# Quad_FC_V10_2.net
KiCad netlist of a schematic drawn in Altium Designer
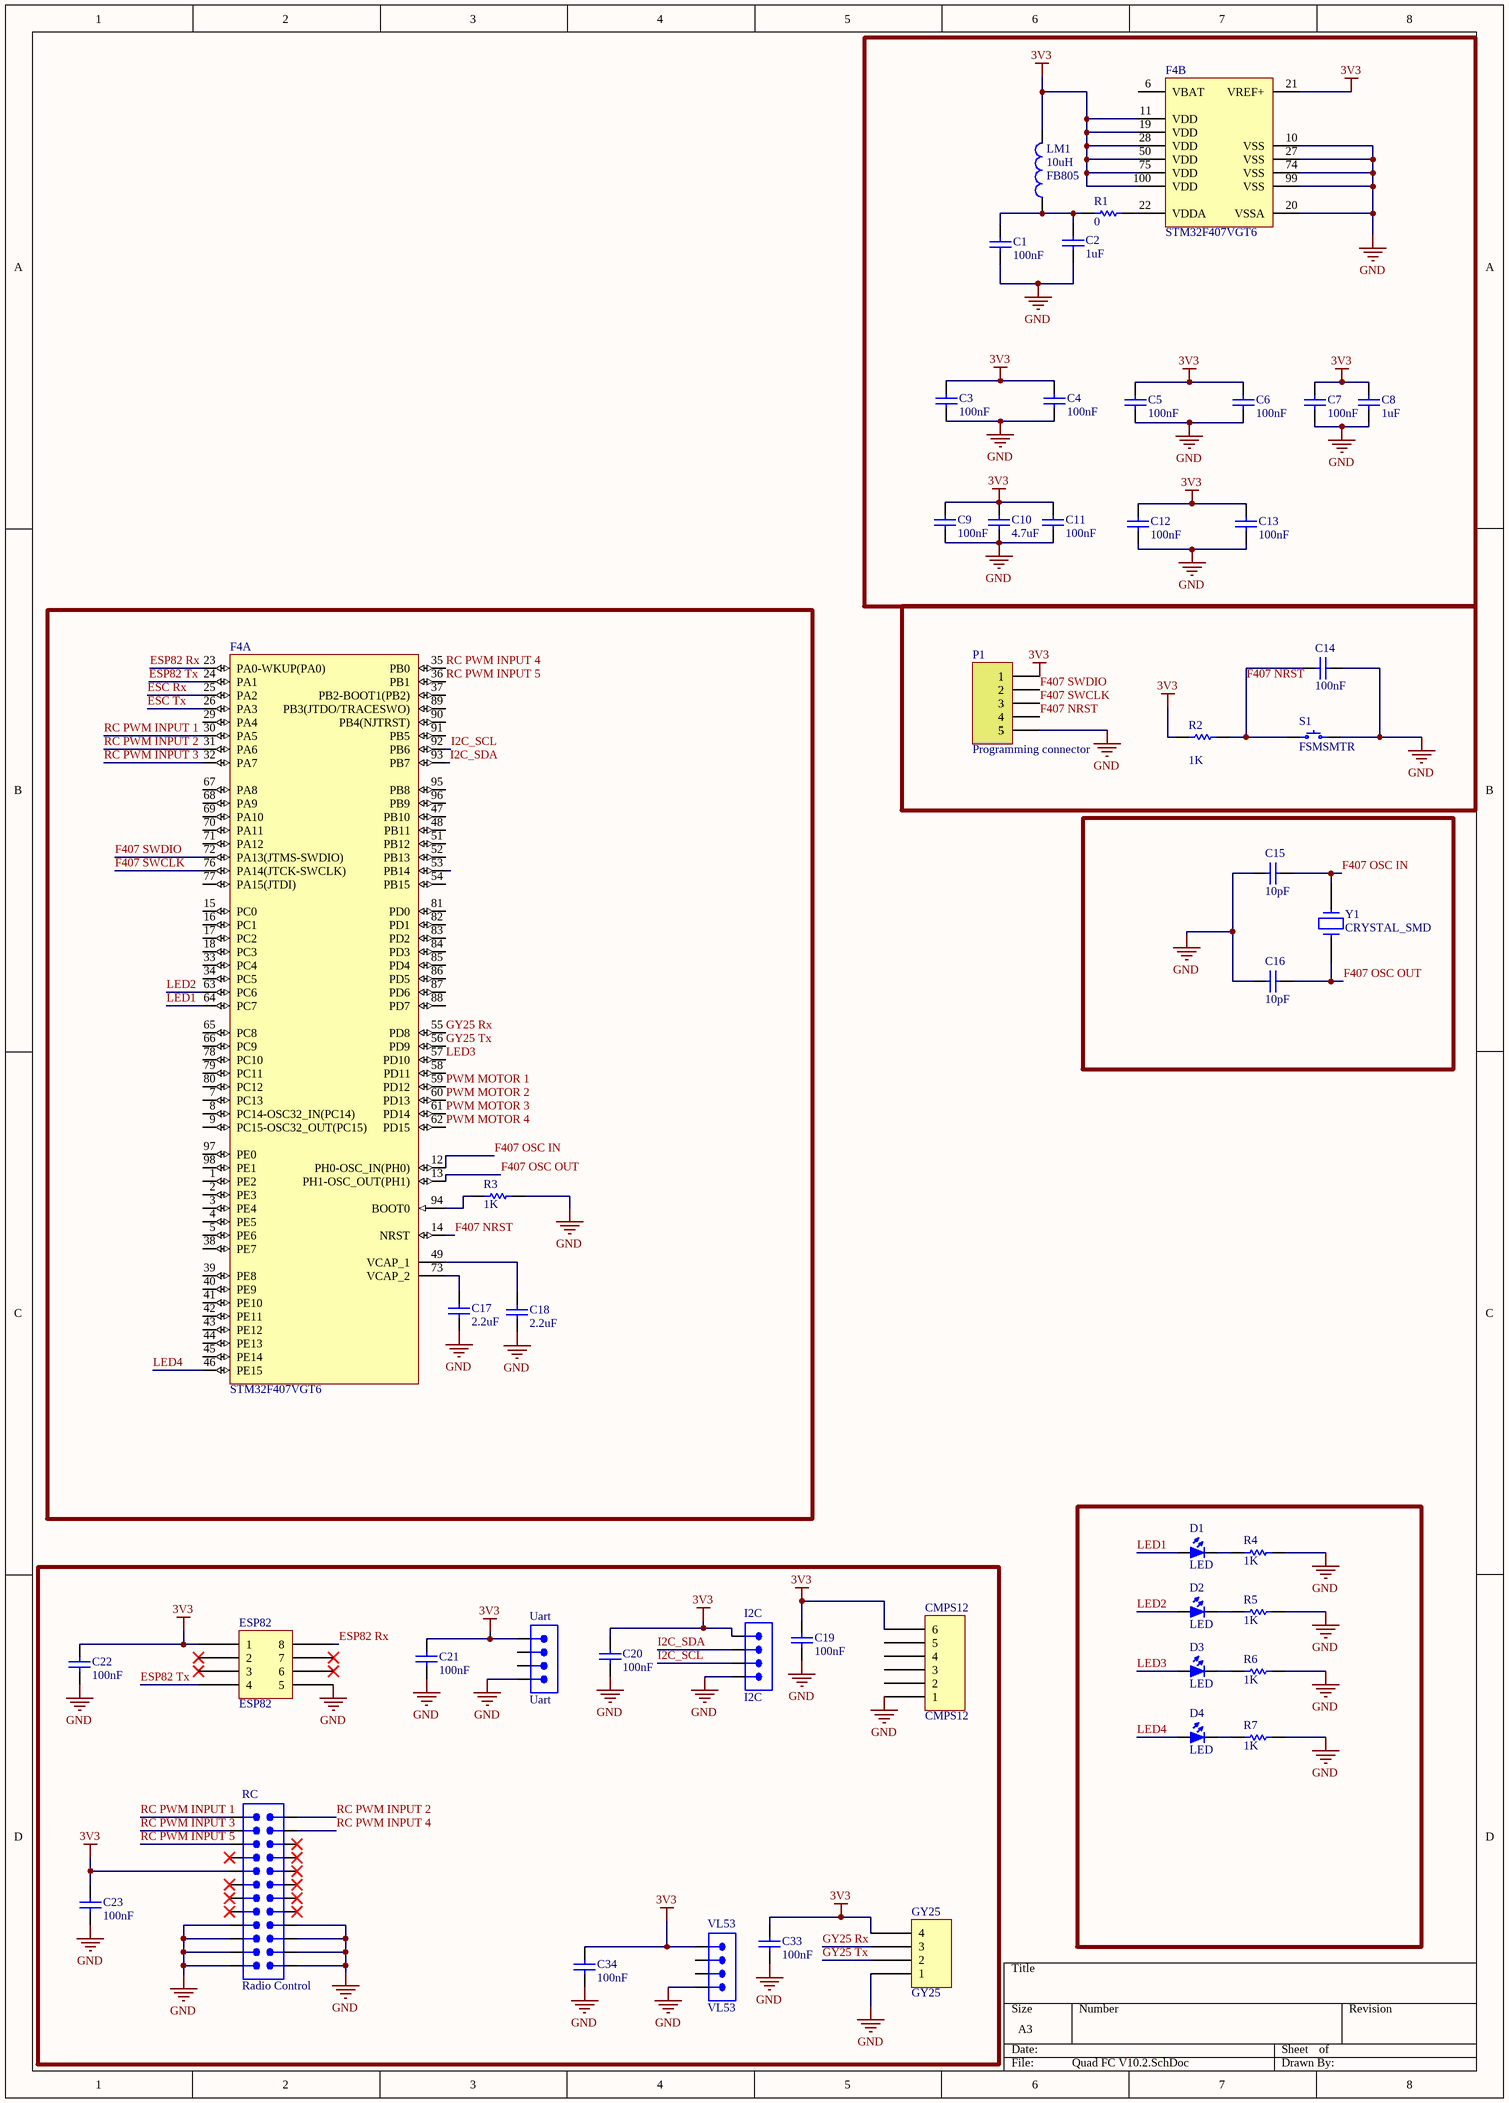
[diagram p0: Quad FC V10.2.SchDoc]

(export (version "E")
  (design (tool "Eeschema 10.0.6"))
  (components
    (comp (ref "C1")
      (value "100nF")
      (footprint "CAP0603")
      (description "F407VET6 Power CAP")
      (fields (field (name "DESIGNER") "Abbas Basereh"))
      (libsource (lib "2017AbbasBasereh9365731239 -ver1") (part "CAP SMD PACKAGE"))
    )
    (comp (ref "C2")
      (value "1uF")
      (footprint "CAP0603")
      (description "F407VET6 Power CAP")
      (fields (field (name "DESIGNER") "Abbas Basereh"))
      (libsource (lib "2017AbbasBasereh9365731239 -ver1") (part "CAP SMD PACKAGE"))
    )
    (comp (ref "C3")
      (value "100nF")
      (footprint "CAP0603")
      (description "F407VET6 Power CAP")
      (fields (field (name "DESIGNER") "Abbas Basereh"))
      (libsource (lib "2017AbbasBasereh9365731239 -ver1") (part "CAP SMD PACKAGE"))
    )
    (comp (ref "C4")
      (value "100nF")
      (footprint "CAP0603")
      (description "F407VET6 Power CAP")
      (fields (field (name "DESIGNER") "Abbas Basereh"))
      (libsource (lib "2017AbbasBasereh9365731239 -ver1") (part "CAP SMD PACKAGE"))
    )
    (comp (ref "C5")
      (value "100nF")
      (footprint "CAP0603")
      (description "F407VET6 Power CAP")
      (fields (field (name "DESIGNER") "Abbas Basereh"))
      (libsource (lib "2017AbbasBasereh9365731239 -ver1") (part "CAP SMD PACKAGE"))
    )
    (comp (ref "C6")
      (value "100nF")
      (footprint "CAP0603")
      (description "F407VET6 Power CAP")
      (fields (field (name "DESIGNER") "Abbas Basereh"))
      (libsource (lib "2017AbbasBasereh9365731239 -ver1") (part "CAP SMD PACKAGE"))
    )
    (comp (ref "C7")
      (value "100nF")
      (footprint "CAP0603")
      (description "F407VET6 Power CAP")
      (fields (field (name "DESIGNER") "Abbas Basereh"))
      (libsource (lib "2017AbbasBasereh9365731239 -ver1") (part "CAP SMD PACKAGE"))
    )
    (comp (ref "C8")
      (value "1uF")
      (footprint "CAP0603")
      (description "F407VET6 Power CAP")
      (fields (field (name "DESIGNER") "Abbas Basereh"))
      (libsource (lib "2017AbbasBasereh9365731239 -ver1") (part "CAP SMD PACKAGE"))
    )
    (comp (ref "C9")
      (value "100nF")
      (footprint "CAP0603")
      (description "F407VET6 Power CAP")
      (fields (field (name "DESIGNER") "Abbas Basereh"))
      (libsource (lib "2017AbbasBasereh9365731239 -ver1") (part "CAP SMD PACKAGE"))
    )
    (comp (ref "C10")
      (value "4.7uF")
      (footprint "CAP0603")
      (description "F407VET6 Power CAP")
      (fields (field (name "DESIGNER") "Abbas Basereh"))
      (libsource (lib "2017AbbasBasereh9365731239 -ver1") (part "CAP SMD PACKAGE"))
    )
    (comp (ref "C11")
      (value "100nF")
      (footprint "CAP0603")
      (description "F407VET6 Power CAP")
      (fields (field (name "DESIGNER") "Abbas Basereh"))
      (libsource (lib "2017AbbasBasereh9365731239 -ver1") (part "CAP SMD PACKAGE"))
    )
    (comp (ref "C12")
      (value "100nF")
      (footprint "CAP0603")
      (description "F407VET6 Power CAP")
      (fields (field (name "DESIGNER") "Abbas Basereh"))
      (libsource (lib "2017AbbasBasereh9365731239 -ver1") (part "CAP SMD PACKAGE"))
    )
    (comp (ref "C13")
      (value "100nF")
      (footprint "CAP0603")
      (description "F407VET6 Power CAP")
      (fields (field (name "DESIGNER") "Abbas Basereh"))
      (libsource (lib "2017AbbasBasereh9365731239 -ver1") (part "CAP SMD PACKAGE"))
    )
    (comp (ref "C14")
      (value "100nF")
      (footprint "CAP0603")
      (description "F407VET6 Power CAP")
      (fields (field (name "DESIGNER") "Abbas Basereh"))
      (libsource (lib "2017AbbasBasereh9365731239 -ver1") (part "CAP SMD PACKAGE"))
    )
    (comp (ref "C15")
      (value "10pF")
      (footprint "CAP0603")
      (description "F407VET6 Power CAP")
      (fields (field (name "DESIGNER") "Abbas Basereh"))
      (libsource (lib "2017AbbasBasereh9365731239 -ver1") (part "CAP SMD PACKAGE"))
    )
    (comp (ref "C16")
      (value "10pF")
      (footprint "CAP0603")
      (description "F407VET6 Power CAP")
      (fields (field (name "DESIGNER") "Abbas Basereh"))
      (libsource (lib "2017AbbasBasereh9365731239 -ver1") (part "CAP SMD PACKAGE"))
    )
    (comp (ref "C17")
      (value "2.2uF")
      (footprint "CAP0603")
      (description "F407VET6 Power CAP")
      (fields (field (name "DESIGNER") "Abbas Basereh"))
      (libsource (lib "2017AbbasBasereh9365731239 -ver1") (part "CAP SMD PACKAGE"))
    )
    (comp (ref "C18")
      (value "2.2uF")
      (footprint "CAP0603")
      (description "F407VET6 Power CAP")
      (fields (field (name "DESIGNER") "Abbas Basereh"))
      (libsource (lib "2017AbbasBasereh9365731239 -ver1") (part "CAP SMD PACKAGE"))
    )
    (comp (ref "C19")
      (value "100nF")
      (footprint "CAP0603")
      (description "F407VET6 Power CAP")
      (fields (field (name "DESIGNER") "Abbas Basereh"))
      (libsource (lib "2017AbbasBasereh9365731239 -ver1") (part "CAP SMD PACKAGE"))
    )
    (comp (ref "C20")
      (value "100nF")
      (footprint "CAP0603")
      (description "F407VET6 Power CAP")
      (fields (field (name "DESIGNER") "Abbas Basereh"))
      (libsource (lib "2017AbbasBasereh9365731239 -ver1") (part "CAP SMD PACKAGE"))
    )
    (comp (ref "C21")
      (value "100nF")
      (footprint "CAP0603")
      (description "F407VET6 Power CAP")
      (fields (field (name "DESIGNER") "Abbas Basereh"))
      (libsource (lib "2017AbbasBasereh9365731239 -ver1") (part "CAP SMD PACKAGE"))
    )
    (comp (ref "C22")
      (value "100nF")
      (footprint "CAP0603")
      (description "F407VET6 Power CAP")
      (fields (field (name "DESIGNER") "Abbas Basereh"))
      (libsource (lib "2017AbbasBasereh9365731239 -ver1") (part "CAP SMD PACKAGE"))
    )
    (comp (ref "C23")
      (value "100nF")
      (footprint "CAP0603")
      (description "F407VET6 Power CAP")
      (fields (field (name "DESIGNER") "Abbas Basereh"))
      (libsource (lib "2017AbbasBasereh9365731239 -ver1") (part "CAP SMD PACKAGE"))
    )
    (comp (ref "C33")
      (value "100nF")
      (footprint "CAP0603")
      (description "F407VET6 Power CAP")
      (fields (field (name "DESIGNER") "Abbas Basereh"))
      (libsource (lib "2017AbbasBasereh9365731239 -ver1") (part "CAP SMD PACKAGE"))
    )
    (comp (ref "C34")
      (value "100nF")
      (footprint "CAP0603")
      (description "F407VET6 Power CAP")
      (fields (field (name "DESIGNER") "Abbas Basereh"))
      (libsource (lib "2017AbbasBasereh9365731239 -ver1") (part "CAP SMD PACKAGE"))
    )
    (comp (ref "CMPS12")
      (value "CMPS12")
      (footprint "SAMTEC SSW-106-03-T-S")
      (description "CONN RCPT 6POS 0.1 TIN PCB")
      (fields (field (name "PART NUMBER") "SSW-106-03-T-S") (field (name "MANUFACTURER") "Samtec Inc."))
      (libsource (lib "Celestial Altium Library - altium_library (1)") (part "6 Pin"))
    )
    (comp (ref "D1")
      (value "LED")
      (footprint "0603 - LED")
      (description "Led")
      (fields (field (name "PUBLISHER") "Altium Limited"))
      (libsource (lib "Sajad_Altium_Library") (part "LED"))
    )
    (comp (ref "D2")
      (value "LED")
      (footprint "0603 - LED")
      (description "Led")
      (fields (field (name "PUBLISHER") "Altium Limited"))
      (libsource (lib "Sajad_Altium_Library") (part "LED"))
    )
    (comp (ref "D3")
      (value "LED")
      (footprint "0603 - LED")
      (description "Led")
      (fields (field (name "PUBLISHER") "Altium Limited"))
      (libsource (lib "Sajad_Altium_Library") (part "LED"))
    )
    (comp (ref "D4")
      (value "LED")
      (footprint "0603 - LED")
      (description "Led")
      (fields (field (name "PUBLISHER") "Altium Limited"))
      (libsource (lib "Sajad_Altium_Library") (part "LED"))
    )
    (comp (ref "ESP82")
      (value "ESP82")
      (footprint "HARWIN M20-7830445")
      (description "CONN RCPT 8POS 0.1 GOLD PCB")
      (fields (field (name "PART NUMBER") "M20-7830442") (field (name "MANUFACTURER") "Harwin Inc."))
      (libsource (lib "Celestial Altium Library - altium_library (1)") (part "2X4 PIN DU"))
    )
    (comp (ref "F4")
      (value "STM32F407VGT6")
      (footprint "STM-LQFP100_N")
      (fields (field (name "MANUFACTURER") "STMicroelectronics"))
      (libsource (lib "STMicroelectronics STM32 F4") (part "STM32F407VGT6"))
    )
    (comp (ref "GY25")
      (value "GY25")
      (footprint "SAMTEC SSW-104-03-T-S")
      (description "CONN RCPT 4POS 0.1 TIN PCB")
      (fields (field (name "PART NUMBER") "SSW-104-03-T-S") (field (name "MANUFACTURER") "Samtec Inc."))
      (libsource (lib "Celestial Altium Library - altium_library (1)") (part "4 Pin"))
    )
    (comp (ref "I2C")
      (value "I2C")
      (footprint "JST BM04B-SURS-TF")
      (description "Male Header 1X04")
      (libsource (lib "SJ Sockets & Connectors") (part "MHDR_1X04"))
    )
    (comp (ref "LM1")
      (value "10uH")
      (footprint "0805L")
      (description "Inductor")
      (fields (field (name "ALTIUM_VALUE") "FB805") (field (name "PUBLISHER") "Altium Limited"))
      (libsource (lib "2017AbbasBasereh9365731239 -ver1") (part "L SMA 0.25W"))
    )
    (comp (ref "P1")
      (value "Programming connector")
      (footprint "Connector1X5")
      (description "Connector, 5-Pin2.5mm")
      (fields (field (name "PUBLISHER") "Altium Limited"))
      (libsource (lib "Sajad_Altium_Library") (part "Connector1x5"))
    )
    (comp (ref "R1")
      (value "0")
      (footprint "RES0603")
      (description "TOTAL SMD RESISTOR PACK")
      (fields (field (name "DESIGNER") "Abbas Basereh"))
      (libsource (lib "2017AbbasBasereh9365731239 -ver1") (part "RES SMD PACKAGE"))
    )
    (comp (ref "R2")
      (value "1K")
      (footprint "RES0603")
      (description "TOTAL SMD RESISTOR PACK")
      (fields (field (name "DESIGNER") "Abbas Basereh"))
      (libsource (lib "2017AbbasBasereh9365731239 -ver1") (part "RES SMD PACKAGE"))
    )
    (comp (ref "R3")
      (value "1K")
      (footprint "RES0603")
      (description "TOTAL SMD RESISTOR PACK")
      (fields (field (name "DESIGNER") "Abbas Basereh"))
      (libsource (lib "2017AbbasBasereh9365731239 -ver1") (part "RES SMD PACKAGE"))
    )
    (comp (ref "R4")
      (value "1K")
      (footprint "RES0603")
      (description "TOTAL SMD RESISTOR PACK")
      (fields (field (name "DESIGNER") "Abbas Basereh"))
      (libsource (lib "2017AbbasBasereh9365731239 -ver1") (part "RES SMD PACKAGE"))
    )
    (comp (ref "R5")
      (value "1K")
      (footprint "RES0603")
      (description "TOTAL SMD RESISTOR PACK")
      (fields (field (name "DESIGNER") "Abbas Basereh"))
      (libsource (lib "2017AbbasBasereh9365731239 -ver1") (part "RES SMD PACKAGE"))
    )
    (comp (ref "R6")
      (value "1K")
      (footprint "RES0603")
      (description "TOTAL SMD RESISTOR PACK")
      (fields (field (name "DESIGNER") "Abbas Basereh"))
      (libsource (lib "2017AbbasBasereh9365731239 -ver1") (part "RES SMD PACKAGE"))
    )
    (comp (ref "R7")
      (value "1K")
      (footprint "RES0603")
      (description "TOTAL SMD RESISTOR PACK")
      (fields (field (name "DESIGNER") "Abbas Basereh"))
      (libsource (lib "2017AbbasBasereh9365731239 -ver1") (part "RES SMD PACKAGE"))
    )
    (comp (ref "RC")
      (value "Radio Control")
      (footprint "HEADER8X3:HEADER8X3")
      (description "Male Header 2X12")
      (libsource (lib "SJ Sockets & Connectors") (part "MHDR_2X12"))
    )
    (comp (ref "S1")
      (value "FSMSMTR")
      (footprint "TE FSMSMTR")
      (description "SWITCH TACTILE SPST-NO 0.05A 24V")
      (fields (field (name "MANUFACTURER") "TE Connectivity ALCOSWITCH Switches"))
      (libsource (lib "Celestial Altium Library - altium_library (1)") (part "SPST-NO 2 PIN"))
    )
    (comp (ref "Uart")
      (value "Uart")
      (footprint "JST BM04B-SURS-TF")
      (description "Male Header 1X04")
      (libsource (lib "SJ Sockets & Connectors") (part "MHDR_1X04"))
    )
    (comp (ref "VL53")
      (value "VL53")
      (footprint "JST BM04B-SURS-TF")
      (description "Male Header 1X04")
      (libsource (lib "SJ Sockets & Connectors") (part "MHDR_1X04"))
    )
    (comp (ref "Y1")
      (value "CRYSTAL_SMD")
      (footprint "My_Crystal - SMD")
      (description "Crystal")
      (libsource (lib "AMINLIB") (part "CRYSTAL_SMD"))
    )
  )
  (nets
    (net (code "1") (name "/ESC Rx") (class "Default")
      (node (ref "F4") (pin "25") (pinfunction "PA2_25") (pintype "bidirectional"))
    )
    (net (code "2") (name "/ESC Tx") (class "Default")
      (node (ref "F4") (pin "26") (pinfunction "PA3_26") (pintype "bidirectional"))
    )
    (net (code "3") (name "/ESP82 Rx") (class "Default")
      (node (ref "ESP82") (pin "8") (pinfunction "8_8") (pintype "passive"))
      (node (ref "F4") (pin "23") (pinfunction "PA0-WKUP(PA0)_23") (pintype "bidirectional"))
    )
    (net (code "4") (name "/ESP82 Tx") (class "Default")
      (node (ref "ESP82") (pin "4") (pinfunction "4_4") (pintype "passive"))
      (node (ref "F4") (pin "24") (pinfunction "PA1_24") (pintype "bidirectional"))
    )
    (net (code "5") (name "/F407 NRST") (class "Default")
      (node (ref "C14") (pin "1") (pinfunction "1_1") (pintype "passive"))
      (node (ref "F4") (pin "14") (pinfunction "NRST_14") (pintype "bidirectional"))
      (node (ref "P1") (pin "4") (pinfunction "4_4") (pintype "passive"))
      (node (ref "R2") (pin "2") (pinfunction "2_2") (pintype "passive"))
      (node (ref "S1") (pin "1") (pinfunction "1_1") (pintype "passive"))
    )
    (net (code "6") (name "/F407 OSC IN") (class "Default")
      (node (ref "C15") (pin "2") (pinfunction "2_2") (pintype "passive"))
      (node (ref "F4") (pin "12") (pinfunction "PH0-OSC_IN(PH0)_12") (pintype "bidirectional"))
      (node (ref "Y1") (pin "2") (pinfunction "2_2") (pintype "passive"))
    )
    (net (code "7") (name "/F407 OSC OUT") (class "Default")
      (node (ref "C16") (pin "1") (pinfunction "1_1") (pintype "passive"))
      (node (ref "F4") (pin "13") (pinfunction "PH1-OSC_OUT(PH1)_13") (pintype "bidirectional"))
      (node (ref "Y1") (pin "1") (pinfunction "1_1") (pintype "passive"))
    )
    (net (code "8") (name "/F407 SWCLK") (class "Default")
      (node (ref "F4") (pin "76") (pinfunction "PA14(JTCK-SWCLK)_76") (pintype "bidirectional"))
      (node (ref "P1") (pin "3") (pinfunction "3_3") (pintype "passive"))
    )
    (net (code "9") (name "/F407 SWDIO") (class "Default")
      (node (ref "F4") (pin "72") (pinfunction "PA13(JTMS-SWDIO)_72") (pintype "bidirectional"))
      (node (ref "P1") (pin "2") (pinfunction "2_2") (pintype "passive"))
    )
    (net (code "10") (name "/GY25 Rx") (class "Default")
      (node (ref "F4") (pin "55") (pinfunction "PD8_55") (pintype "bidirectional"))
      (node (ref "GY25") (pin "3") (pinfunction "3_3") (pintype "passive"))
    )
    (net (code "11") (name "/GY25 Tx") (class "Default")
      (node (ref "F4") (pin "56") (pinfunction "PD9_56") (pintype "bidirectional"))
      (node (ref "GY25") (pin "2") (pinfunction "2_2") (pintype "passive"))
    )
    (net (code "12") (name "/I2C_SCL") (class "Default")
      (node (ref "F4") (pin "92") (pinfunction "PB6_92") (pintype "bidirectional"))
      (node (ref "I2C") (pin "3") (pinfunction "3_3") (pintype "passive"))
    )
    (net (code "13") (name "/I2C_SDA") (class "Default")
      (node (ref "F4") (pin "93") (pinfunction "PB7_93") (pintype "bidirectional"))
      (node (ref "I2C") (pin "2") (pinfunction "2_2") (pintype "passive"))
    )
    (net (code "14") (name "/LED1") (class "Default")
      (node (ref "D1") (pin "1") (pinfunction "A_1") (pintype "passive"))
      (node (ref "F4") (pin "64") (pinfunction "PC7_64") (pintype "bidirectional"))
    )
    (net (code "15") (name "/LED2") (class "Default")
      (node (ref "D2") (pin "1") (pinfunction "A_1") (pintype "passive"))
      (node (ref "F4") (pin "63") (pinfunction "PC6_63") (pintype "bidirectional"))
    )
    (net (code "16") (name "/LED3") (class "Default")
      (node (ref "D3") (pin "1") (pinfunction "A_1") (pintype "passive"))
      (node (ref "F4") (pin "57") (pinfunction "PD10_57") (pintype "bidirectional"))
    )
    (net (code "17") (name "/LED4") (class "Default")
      (node (ref "D4") (pin "1") (pinfunction "A_1") (pintype "passive"))
      (node (ref "F4") (pin "46") (pinfunction "PE15_46") (pintype "bidirectional"))
    )
    (net (code "18") (name "/PWM MOTOR 1") (class "Default")
      (node (ref "F4") (pin "59") (pinfunction "PD12_59") (pintype "bidirectional"))
    )
    (net (code "19") (name "/PWM MOTOR 2") (class "Default")
      (node (ref "F4") (pin "60") (pinfunction "PD13_60") (pintype "bidirectional"))
    )
    (net (code "20") (name "/PWM MOTOR 3") (class "Default")
      (node (ref "F4") (pin "61") (pinfunction "PD14_61") (pintype "bidirectional"))
    )
    (net (code "21") (name "/PWM MOTOR 4") (class "Default")
      (node (ref "F4") (pin "62") (pinfunction "PD15_62") (pintype "bidirectional"))
    )
    (net (code "22") (name "/RC PWM INPUT 1") (class "Default")
      (node (ref "F4") (pin "30") (pinfunction "PA5_30") (pintype "bidirectional"))
      (node (ref "RC") (pin "1") (pinfunction "1_1") (pintype "passive"))
    )
    (net (code "23") (name "/RC PWM INPUT 2") (class "Default")
      (node (ref "F4") (pin "31") (pinfunction "PA6_31") (pintype "bidirectional"))
      (node (ref "RC") (pin "2") (pinfunction "2_2") (pintype "passive"))
    )
    (net (code "24") (name "/RC PWM INPUT 3") (class "Default")
      (node (ref "F4") (pin "32") (pinfunction "PA7_32") (pintype "bidirectional"))
      (node (ref "RC") (pin "3") (pinfunction "3_3") (pintype "passive"))
    )
    (net (code "25") (name "/RC PWM INPUT 4") (class "Default")
      (node (ref "F4") (pin "35") (pinfunction "PB0_35") (pintype "bidirectional"))
      (node (ref "RC") (pin "4") (pinfunction "4_4") (pintype "passive"))
    )
    (net (code "26") (name "/RC PWM INPUT 5") (class "Default")
      (node (ref "F4") (pin "36") (pinfunction "PB1_36") (pintype "bidirectional"))
      (node (ref "RC") (pin "5") (pinfunction "5_5") (pintype "passive"))
    )
    (net (code "27") (name "3V3") (class "Default")
      (node (ref "C10") (pin "2") (pinfunction "2_2") (pintype "passive"))
      (node (ref "C11") (pin "2") (pinfunction "2_2") (pintype "passive"))
      (node (ref "C12") (pin "2") (pinfunction "2_2") (pintype "passive"))
      (node (ref "C13") (pin "2") (pinfunction "2_2") (pintype "passive"))
      (node (ref "C19") (pin "1") (pinfunction "1_1") (pintype "passive"))
      (node (ref "C20") (pin "1") (pinfunction "1_1") (pintype "passive"))
      (node (ref "C21") (pin "1") (pinfunction "1_1") (pintype "passive"))
      (node (ref "C22") (pin "1") (pinfunction "1_1") (pintype "passive"))
      (node (ref "C23") (pin "1") (pinfunction "1_1") (pintype "passive"))
      (node (ref "C3") (pin "2") (pinfunction "2_2") (pintype "passive"))
      (node (ref "C33") (pin "1") (pinfunction "1_1") (pintype "passive"))
      (node (ref "C34") (pin "1") (pinfunction "1_1") (pintype "passive"))
      (node (ref "C4") (pin "2") (pinfunction "2_2") (pintype "passive"))
      (node (ref "C5") (pin "2") (pinfunction "2_2") (pintype "passive"))
      (node (ref "C6") (pin "2") (pinfunction "2_2") (pintype "passive"))
      (node (ref "C7") (pin "1") (pinfunction "1_1") (pintype "passive"))
      (node (ref "C8") (pin "1") (pinfunction "1_1") (pintype "passive"))
      (node (ref "C9") (pin "2") (pinfunction "2_2") (pintype "passive"))
      (node (ref "CMPS12") (pin "6") (pinfunction "6_6") (pintype "passive"))
      (node (ref "ESP82") (pin "1") (pinfunction "1_1") (pintype "passive"))
      (node (ref "F4") (pin "100") (pinfunction "VDD_100") (pintype "power_in"))
      (node (ref "F4") (pin "11") (pinfunction "VDD_11") (pintype "power_in"))
      (node (ref "F4") (pin "19") (pinfunction "VDD_19") (pintype "power_in"))
      (node (ref "F4") (pin "21") (pinfunction "VREF+_21") (pintype "power_in"))
      (node (ref "F4") (pin "28") (pinfunction "VDD_28") (pintype "power_in"))
      (node (ref "F4") (pin "50") (pinfunction "VDD_50") (pintype "power_in"))
      (node (ref "F4") (pin "75") (pinfunction "VDD_75") (pintype "power_in"))
      (node (ref "GY25") (pin "4") (pinfunction "4_4") (pintype "passive"))
      (node (ref "I2C") (pin "1") (pinfunction "1_1") (pintype "passive"))
      (node (ref "LM1") (pin "2") (pinfunction "2_2") (pintype "passive"))
      (node (ref "P1") (pin "1") (pinfunction "1_1") (pintype "passive"))
      (node (ref "R2") (pin "1") (pinfunction "1_1") (pintype "passive"))
      (node (ref "RC") (pin "9") (pinfunction "9_9") (pintype "passive"))
      (node (ref "Uart") (pin "1") (pinfunction "1_1") (pintype "passive"))
      (node (ref "VL53") (pin "1") (pinfunction "1_1") (pintype "passive"))
    )
    (net (code "28") (name "GND") (class "Default")
      (node (ref "C1") (pin "1") (pinfunction "1_1") (pintype "passive"))
      (node (ref "C10") (pin "1") (pinfunction "1_1") (pintype "passive"))
      (node (ref "C11") (pin "1") (pinfunction "1_1") (pintype "passive"))
      (node (ref "C12") (pin "1") (pinfunction "1_1") (pintype "passive"))
      (node (ref "C13") (pin "1") (pinfunction "1_1") (pintype "passive"))
      (node (ref "C14") (pin "2") (pinfunction "2_2") (pintype "passive"))
      (node (ref "C15") (pin "1") (pinfunction "1_1") (pintype "passive"))
      (node (ref "C16") (pin "2") (pinfunction "2_2") (pintype "passive"))
      (node (ref "C17") (pin "2") (pinfunction "2_2") (pintype "passive"))
      (node (ref "C18") (pin "2") (pinfunction "2_2") (pintype "passive"))
      (node (ref "C19") (pin "2") (pinfunction "2_2") (pintype "passive"))
      (node (ref "C2") (pin "1") (pinfunction "1_1") (pintype "passive"))
      (node (ref "C20") (pin "2") (pinfunction "2_2") (pintype "passive"))
      (node (ref "C21") (pin "2") (pinfunction "2_2") (pintype "passive"))
      (node (ref "C22") (pin "2") (pinfunction "2_2") (pintype "passive"))
      (node (ref "C23") (pin "2") (pinfunction "2_2") (pintype "passive"))
      (node (ref "C3") (pin "1") (pinfunction "1_1") (pintype "passive"))
      (node (ref "C33") (pin "2") (pinfunction "2_2") (pintype "passive"))
      (node (ref "C34") (pin "2") (pinfunction "2_2") (pintype "passive"))
      (node (ref "C4") (pin "1") (pinfunction "1_1") (pintype "passive"))
      (node (ref "C5") (pin "1") (pinfunction "1_1") (pintype "passive"))
      (node (ref "C6") (pin "1") (pinfunction "1_1") (pintype "passive"))
      (node (ref "C7") (pin "2") (pinfunction "2_2") (pintype "passive"))
      (node (ref "C8") (pin "2") (pinfunction "2_2") (pintype "passive"))
      (node (ref "C9") (pin "1") (pinfunction "1_1") (pintype "passive"))
      (node (ref "CMPS12") (pin "1") (pinfunction "1_1") (pintype "passive"))
      (node (ref "ESP82") (pin "5") (pinfunction "5_5") (pintype "passive"))
      (node (ref "F4") (pin "10") (pinfunction "VSS_10") (pintype "power_in"))
      (node (ref "F4") (pin "20") (pinfunction "VSSA_20") (pintype "power_in"))
      (node (ref "F4") (pin "27") (pinfunction "VSS_27") (pintype "power_in"))
      (node (ref "F4") (pin "74") (pinfunction "VSS_74") (pintype "power_in"))
      (node (ref "F4") (pin "99") (pinfunction "VSS_99") (pintype "power_in"))
      (node (ref "GY25") (pin "1") (pinfunction "1_1") (pintype "passive"))
      (node (ref "I2C") (pin "4") (pinfunction "4_4") (pintype "passive"))
      (node (ref "P1") (pin "5") (pinfunction "5_5") (pintype "passive"))
      (node (ref "R3") (pin "2") (pinfunction "2_2") (pintype "passive"))
      (node (ref "R4") (pin "2") (pinfunction "2_2") (pintype "passive"))
      (node (ref "R5") (pin "2") (pinfunction "2_2") (pintype "passive"))
      (node (ref "R6") (pin "2") (pinfunction "2_2") (pintype "passive"))
      (node (ref "R7") (pin "2") (pinfunction "2_2") (pintype "passive"))
      (node (ref "RC") (pin "17") (pinfunction "17_17") (pintype "passive"))
      (node (ref "RC") (pin "18") (pinfunction "18_18") (pintype "passive"))
      (node (ref "RC") (pin "19") (pinfunction "19_19") (pintype "passive"))
      (node (ref "RC") (pin "20") (pinfunction "20_20") (pintype "passive"))
      (node (ref "RC") (pin "21") (pinfunction "21_21") (pintype "passive"))
      (node (ref "RC") (pin "22") (pinfunction "22_22") (pintype "passive"))
      (node (ref "RC") (pin "23") (pinfunction "23_23") (pintype "passive"))
      (node (ref "RC") (pin "24") (pinfunction "24_24") (pintype "passive"))
      (node (ref "S1") (pin "2") (pinfunction "2_2") (pintype "passive"))
      (node (ref "Uart") (pin "4") (pinfunction "4_4") (pintype "passive"))
      (node (ref "VL53") (pin "4") (pinfunction "4_4") (pintype "passive"))
    )
    (net (code "29") (name "Net-(C1-Pad2)") (class "Default")
      (node (ref "C1") (pin "2") (pinfunction "2_2") (pintype "passive"))
      (node (ref "C2") (pin "2") (pinfunction "2_2") (pintype "passive"))
      (node (ref "LM1") (pin "1") (pinfunction "1_1") (pintype "passive"))
      (node (ref "R1") (pin "1") (pinfunction "1_1") (pintype "passive"))
    )
    (net (code "30") (name "Net-(D1-K)") (class "Default")
      (node (ref "D1") (pin "2") (pinfunction "K_2") (pintype "passive"))
      (node (ref "R4") (pin "1") (pinfunction "1_1") (pintype "passive"))
    )
    (net (code "31") (name "Net-(D2-K)") (class "Default")
      (node (ref "D2") (pin "2") (pinfunction "K_2") (pintype "passive"))
      (node (ref "R5") (pin "1") (pinfunction "1_1") (pintype "passive"))
    )
    (net (code "32") (name "Net-(D3-K)") (class "Default")
      (node (ref "D3") (pin "2") (pinfunction "K_2") (pintype "passive"))
      (node (ref "R6") (pin "1") (pinfunction "1_1") (pintype "passive"))
    )
    (net (code "33") (name "Net-(D4-K)") (class "Default")
      (node (ref "D4") (pin "2") (pinfunction "K_2") (pintype "passive"))
      (node (ref "R7") (pin "1") (pinfunction "1_1") (pintype "passive"))
    )
    (net (code "34") (name "Net-(F4A-BOOT0)") (class "Default")
      (node (ref "F4") (pin "94") (pinfunction "BOOT0_94") (pintype "input"))
      (node (ref "R3") (pin "1") (pinfunction "1_1") (pintype "passive"))
    )
    (net (code "35") (name "Net-(F4A-VCAP_1)") (class "Default")
      (node (ref "C18") (pin "1") (pinfunction "1_1") (pintype "passive"))
      (node (ref "F4") (pin "49") (pinfunction "VCAP_1_49") (pintype "power_in"))
    )
    (net (code "36") (name "Net-(F4A-VCAP_2)") (class "Default")
      (node (ref "C17") (pin "1") (pinfunction "1_1") (pintype "passive"))
      (node (ref "F4") (pin "73") (pinfunction "VCAP_2_73") (pintype "power_in"))
    )
    (net (code "37") (name "Net-(F4B-VDDA)") (class "Default")
      (node (ref "F4") (pin "22") (pinfunction "VDDA_22") (pintype "power_in"))
      (node (ref "R1") (pin "2") (pinfunction "2_2") (pintype "passive"))
    )
    (net (code "38") (name "unconnected-(CMPS12-Pad2)") (class "Default")
      (node (ref "CMPS12") (pin "2") (pinfunction "2_2") (pintype "passive"))
    )
    (net (code "39") (name "unconnected-(CMPS12-Pad3)") (class "Default")
      (node (ref "CMPS12") (pin "3") (pinfunction "3_3") (pintype "passive"))
    )
    (net (code "40") (name "unconnected-(CMPS12-Pad4)") (class "Default")
      (node (ref "CMPS12") (pin "4") (pinfunction "4_4") (pintype "passive"))
    )
    (net (code "41") (name "unconnected-(CMPS12-Pad5)") (class "Default")
      (node (ref "CMPS12") (pin "5") (pinfunction "5_5") (pintype "passive"))
    )
    (net (code "42") (name "unconnected-(ESP82-Pad2)") (class "Default")
      (node (ref "ESP82") (pin "2") (pinfunction "2_2") (pintype "passive+no_connect"))
    )
    (net (code "43") (name "unconnected-(ESP82-Pad3)") (class "Default")
      (node (ref "ESP82") (pin "3") (pinfunction "3_3") (pintype "passive+no_connect"))
    )
    (net (code "44") (name "unconnected-(ESP82-Pad6)") (class "Default")
      (node (ref "ESP82") (pin "6") (pinfunction "6_6") (pintype "passive+no_connect"))
    )
    (net (code "45") (name "unconnected-(ESP82-Pad7)") (class "Default")
      (node (ref "ESP82") (pin "7") (pinfunction "7_7") (pintype "passive+no_connect"))
    )
    (net (code "46") (name "unconnected-(F4A-PA4-Pad29)") (class "Default")
      (node (ref "F4") (pin "29") (pinfunction "PA4_29") (pintype "bidirectional"))
    )
    (net (code "47") (name "unconnected-(F4A-PA8-Pad67)") (class "Default")
      (node (ref "F4") (pin "67") (pinfunction "PA8_67") (pintype "bidirectional"))
    )
    (net (code "48") (name "unconnected-(F4A-PA9-Pad68)") (class "Default")
      (node (ref "F4") (pin "68") (pinfunction "PA9_68") (pintype "bidirectional"))
    )
    (net (code "49") (name "unconnected-(F4A-PA10-Pad69)") (class "Default")
      (node (ref "F4") (pin "69") (pinfunction "PA10_69") (pintype "bidirectional"))
    )
    (net (code "50") (name "unconnected-(F4A-PA11-Pad70)") (class "Default")
      (node (ref "F4") (pin "70") (pinfunction "PA11_70") (pintype "bidirectional"))
    )
    (net (code "51") (name "unconnected-(F4A-PA12-Pad71)") (class "Default")
      (node (ref "F4") (pin "71") (pinfunction "PA12_71") (pintype "bidirectional"))
    )
    (net (code "52") (name "unconnected-(F4A-PA15(JTDI)-Pad77)") (class "Default")
      (node (ref "F4") (pin "77") (pinfunction "PA15(JTDI)_77") (pintype "bidirectional"))
    )
    (net (code "53") (name "unconnected-(F4A-PB2-BOOT1(PB2)-Pad37)") (class "Default")
      (node (ref "F4") (pin "37") (pinfunction "PB2-BOOT1(PB2)_37") (pintype "bidirectional"))
    )
    (net (code "54") (name "unconnected-(F4A-PB3(JTDO{slash}TRACESWO)-Pad89)") (class "Default")
      (node (ref "F4") (pin "89") (pinfunction "PB3(JTDO/TRACESWO)_89") (pintype "bidirectional"))
    )
    (net (code "55") (name "unconnected-(F4A-PB4(NJTRST)-Pad90)") (class "Default")
      (node (ref "F4") (pin "90") (pinfunction "PB4(NJTRST)_90") (pintype "bidirectional"))
    )
    (net (code "56") (name "unconnected-(F4A-PB5-Pad91)") (class "Default")
      (node (ref "F4") (pin "91") (pinfunction "PB5_91") (pintype "bidirectional"))
    )
    (net (code "57") (name "unconnected-(F4A-PB8-Pad95)") (class "Default")
      (node (ref "F4") (pin "95") (pinfunction "PB8_95") (pintype "bidirectional"))
    )
    (net (code "58") (name "unconnected-(F4A-PB9-Pad96)") (class "Default")
      (node (ref "F4") (pin "96") (pinfunction "PB9_96") (pintype "bidirectional"))
    )
    (net (code "59") (name "unconnected-(F4A-PB10-Pad47)") (class "Default")
      (node (ref "F4") (pin "47") (pinfunction "PB10_47") (pintype "bidirectional"))
    )
    (net (code "60") (name "unconnected-(F4A-PB11-Pad48)") (class "Default")
      (node (ref "F4") (pin "48") (pinfunction "PB11_48") (pintype "bidirectional"))
    )
    (net (code "61") (name "unconnected-(F4A-PB12-Pad51)") (class "Default")
      (node (ref "F4") (pin "51") (pinfunction "PB12_51") (pintype "bidirectional"))
    )
    (net (code "62") (name "unconnected-(F4A-PB13-Pad52)") (class "Default")
      (node (ref "F4") (pin "52") (pinfunction "PB13_52") (pintype "bidirectional"))
    )
    (net (code "63") (name "unconnected-(F4A-PB14-Pad53)") (class "Default")
      (node (ref "F4") (pin "53") (pinfunction "PB14_53") (pintype "bidirectional"))
    )
    (net (code "64") (name "unconnected-(F4A-PB15-Pad54)") (class "Default")
      (node (ref "F4") (pin "54") (pinfunction "PB15_54") (pintype "bidirectional"))
    )
    (net (code "65") (name "unconnected-(F4A-PC0-Pad15)") (class "Default")
      (node (ref "F4") (pin "15") (pinfunction "PC0_15") (pintype "bidirectional"))
    )
    (net (code "66") (name "unconnected-(F4A-PC1-Pad16)") (class "Default")
      (node (ref "F4") (pin "16") (pinfunction "PC1_16") (pintype "bidirectional"))
    )
    (net (code "67") (name "unconnected-(F4A-PC2-Pad17)") (class "Default")
      (node (ref "F4") (pin "17") (pinfunction "PC2_17") (pintype "bidirectional"))
    )
    (net (code "68") (name "unconnected-(F4A-PC3-Pad18)") (class "Default")
      (node (ref "F4") (pin "18") (pinfunction "PC3_18") (pintype "bidirectional"))
    )
    (net (code "69") (name "unconnected-(F4A-PC4-Pad33)") (class "Default")
      (node (ref "F4") (pin "33") (pinfunction "PC4_33") (pintype "bidirectional"))
    )
    (net (code "70") (name "unconnected-(F4A-PC5-Pad34)") (class "Default")
      (node (ref "F4") (pin "34") (pinfunction "PC5_34") (pintype "bidirectional"))
    )
    (net (code "71") (name "unconnected-(F4A-PC8-Pad65)") (class "Default")
      (node (ref "F4") (pin "65") (pinfunction "PC8_65") (pintype "bidirectional"))
    )
    (net (code "72") (name "unconnected-(F4A-PC9-Pad66)") (class "Default")
      (node (ref "F4") (pin "66") (pinfunction "PC9_66") (pintype "bidirectional"))
    )
    (net (code "73") (name "unconnected-(F4A-PC10-Pad78)") (class "Default")
      (node (ref "F4") (pin "78") (pinfunction "PC10_78") (pintype "bidirectional"))
    )
    (net (code "74") (name "unconnected-(F4A-PC11-Pad79)") (class "Default")
      (node (ref "F4") (pin "79") (pinfunction "PC11_79") (pintype "bidirectional"))
    )
    (net (code "75") (name "unconnected-(F4A-PC12-Pad80)") (class "Default")
      (node (ref "F4") (pin "80") (pinfunction "PC12_80") (pintype "bidirectional"))
    )
    (net (code "76") (name "unconnected-(F4A-PC13-Pad7)") (class "Default")
      (node (ref "F4") (pin "7") (pinfunction "PC13_7") (pintype "bidirectional"))
    )
    (net (code "77") (name "unconnected-(F4A-PC14-OSC32_IN(PC14)-Pad8)") (class "Default")
      (node (ref "F4") (pin "8") (pinfunction "PC14-OSC32_IN(PC14)_8") (pintype "bidirectional"))
    )
    (net (code "78") (name "unconnected-(F4A-PC15-OSC32_OUT(PC15)-Pad9)") (class "Default")
      (node (ref "F4") (pin "9") (pinfunction "PC15-OSC32_OUT(PC15)_9") (pintype "bidirectional"))
    )
    (net (code "79") (name "unconnected-(F4A-PD0-Pad81)") (class "Default")
      (node (ref "F4") (pin "81") (pinfunction "PD0_81") (pintype "bidirectional"))
    )
    (net (code "80") (name "unconnected-(F4A-PD1-Pad82)") (class "Default")
      (node (ref "F4") (pin "82") (pinfunction "PD1_82") (pintype "bidirectional"))
    )
    (net (code "81") (name "unconnected-(F4A-PD2-Pad83)") (class "Default")
      (node (ref "F4") (pin "83") (pinfunction "PD2_83") (pintype "bidirectional"))
    )
    (net (code "82") (name "unconnected-(F4A-PD3-Pad84)") (class "Default")
      (node (ref "F4") (pin "84") (pinfunction "PD3_84") (pintype "bidirectional"))
    )
    (net (code "83") (name "unconnected-(F4A-PD4-Pad85)") (class "Default")
      (node (ref "F4") (pin "85") (pinfunction "PD4_85") (pintype "bidirectional"))
    )
    (net (code "84") (name "unconnected-(F4A-PD5-Pad86)") (class "Default")
      (node (ref "F4") (pin "86") (pinfunction "PD5_86") (pintype "bidirectional"))
    )
    (net (code "85") (name "unconnected-(F4A-PD6-Pad87)") (class "Default")
      (node (ref "F4") (pin "87") (pinfunction "PD6_87") (pintype "bidirectional"))
    )
    (net (code "86") (name "unconnected-(F4A-PD7-Pad88)") (class "Default")
      (node (ref "F4") (pin "88") (pinfunction "PD7_88") (pintype "bidirectional"))
    )
    (net (code "87") (name "unconnected-(F4A-PD11-Pad58)") (class "Default")
      (node (ref "F4") (pin "58") (pinfunction "PD11_58") (pintype "bidirectional"))
    )
    (net (code "88") (name "unconnected-(F4A-PE0-Pad97)") (class "Default")
      (node (ref "F4") (pin "97") (pinfunction "PE0_97") (pintype "bidirectional"))
    )
    (net (code "89") (name "unconnected-(F4A-PE1-Pad98)") (class "Default")
      (node (ref "F4") (pin "98") (pinfunction "PE1_98") (pintype "bidirectional"))
    )
    (net (code "90") (name "unconnected-(F4A-PE2-Pad1)") (class "Default")
      (node (ref "F4") (pin "1") (pinfunction "PE2_1") (pintype "bidirectional"))
    )
    (net (code "91") (name "unconnected-(F4A-PE3-Pad2)") (class "Default")
      (node (ref "F4") (pin "2") (pinfunction "PE3_2") (pintype "bidirectional"))
    )
    (net (code "92") (name "unconnected-(F4A-PE4-Pad3)") (class "Default")
      (node (ref "F4") (pin "3") (pinfunction "PE4_3") (pintype "bidirectional"))
    )
    (net (code "93") (name "unconnected-(F4A-PE5-Pad4)") (class "Default")
      (node (ref "F4") (pin "4") (pinfunction "PE5_4") (pintype "bidirectional"))
    )
    (net (code "94") (name "unconnected-(F4A-PE6-Pad5)") (class "Default")
      (node (ref "F4") (pin "5") (pinfunction "PE6_5") (pintype "bidirectional"))
    )
    (net (code "95") (name "unconnected-(F4A-PE7-Pad38)") (class "Default")
      (node (ref "F4") (pin "38") (pinfunction "PE7_38") (pintype "bidirectional"))
    )
    (net (code "96") (name "unconnected-(F4A-PE8-Pad39)") (class "Default")
      (node (ref "F4") (pin "39") (pinfunction "PE8_39") (pintype "bidirectional"))
    )
    (net (code "97") (name "unconnected-(F4A-PE9-Pad40)") (class "Default")
      (node (ref "F4") (pin "40") (pinfunction "PE9_40") (pintype "bidirectional"))
    )
    (net (code "98") (name "unconnected-(F4A-PE10-Pad41)") (class "Default")
      (node (ref "F4") (pin "41") (pinfunction "PE10_41") (pintype "bidirectional"))
    )
    (net (code "99") (name "unconnected-(F4A-PE11-Pad42)") (class "Default")
      (node (ref "F4") (pin "42") (pinfunction "PE11_42") (pintype "bidirectional"))
    )
    (net (code "100") (name "unconnected-(F4A-PE12-Pad43)") (class "Default")
      (node (ref "F4") (pin "43") (pinfunction "PE12_43") (pintype "bidirectional"))
    )
    (net (code "101") (name "unconnected-(F4A-PE13-Pad44)") (class "Default")
      (node (ref "F4") (pin "44") (pinfunction "PE13_44") (pintype "bidirectional"))
    )
    (net (code "102") (name "unconnected-(F4A-PE14-Pad45)") (class "Default")
      (node (ref "F4") (pin "45") (pinfunction "PE14_45") (pintype "bidirectional"))
    )
    (net (code "103") (name "unconnected-(F4B-VBAT-Pad6)") (class "Default")
      (node (ref "F4") (pin "6") (pinfunction "VBAT_6") (pintype "power_in"))
    )
    (net (code "104") (name "unconnected-(RC-Pad6)") (class "Default")
      (node (ref "RC") (pin "6") (pinfunction "6_6") (pintype "passive+no_connect"))
    )
    (net (code "105") (name "unconnected-(RC-Pad7)") (class "Default")
      (node (ref "RC") (pin "7") (pinfunction "7_7") (pintype "passive+no_connect"))
    )
    (net (code "106") (name "unconnected-(RC-Pad8)") (class "Default")
      (node (ref "RC") (pin "8") (pinfunction "8_8") (pintype "passive+no_connect"))
    )
    (net (code "107") (name "unconnected-(RC-Pad10)") (class "Default")
      (node (ref "RC") (pin "10") (pinfunction "10_10") (pintype "passive+no_connect"))
    )
    (net (code "108") (name "unconnected-(RC-Pad11)") (class "Default")
      (node (ref "RC") (pin "11") (pinfunction "11_11") (pintype "passive+no_connect"))
    )
    (net (code "109") (name "unconnected-(RC-Pad12)") (class "Default")
      (node (ref "RC") (pin "12") (pinfunction "12_12") (pintype "passive+no_connect"))
    )
    (net (code "110") (name "unconnected-(RC-Pad13)") (class "Default")
      (node (ref "RC") (pin "13") (pinfunction "13_13") (pintype "passive+no_connect"))
    )
    (net (code "111") (name "unconnected-(RC-Pad14)") (class "Default")
      (node (ref "RC") (pin "14") (pinfunction "14_14") (pintype "passive+no_connect"))
    )
    (net (code "112") (name "unconnected-(RC-Pad15)") (class "Default")
      (node (ref "RC") (pin "15") (pinfunction "15_15") (pintype "passive+no_connect"))
    )
    (net (code "113") (name "unconnected-(RC-Pad16)") (class "Default")
      (node (ref "RC") (pin "16") (pinfunction "16_16") (pintype "passive+no_connect"))
    )
    (net (code "114") (name "unconnected-(Uart-Pad2)") (class "Default")
      (node (ref "Uart") (pin "2") (pinfunction "2_2") (pintype "passive"))
    )
    (net (code "115") (name "unconnected-(Uart-Pad3)") (class "Default")
      (node (ref "Uart") (pin "3") (pinfunction "3_3") (pintype "passive"))
    )
    (net (code "116") (name "unconnected-(VL53-Pad2)") (class "Default")
      (node (ref "VL53") (pin "2") (pinfunction "2_2") (pintype "passive"))
    )
    (net (code "117") (name "unconnected-(VL53-Pad3)") (class "Default")
      (node (ref "VL53") (pin "3") (pinfunction "3_3") (pintype "passive"))
    )
  )
)
